# Ananas-core-0_9_2-no340G.net
KiCad netlist of a schematic drawn in EAGLE
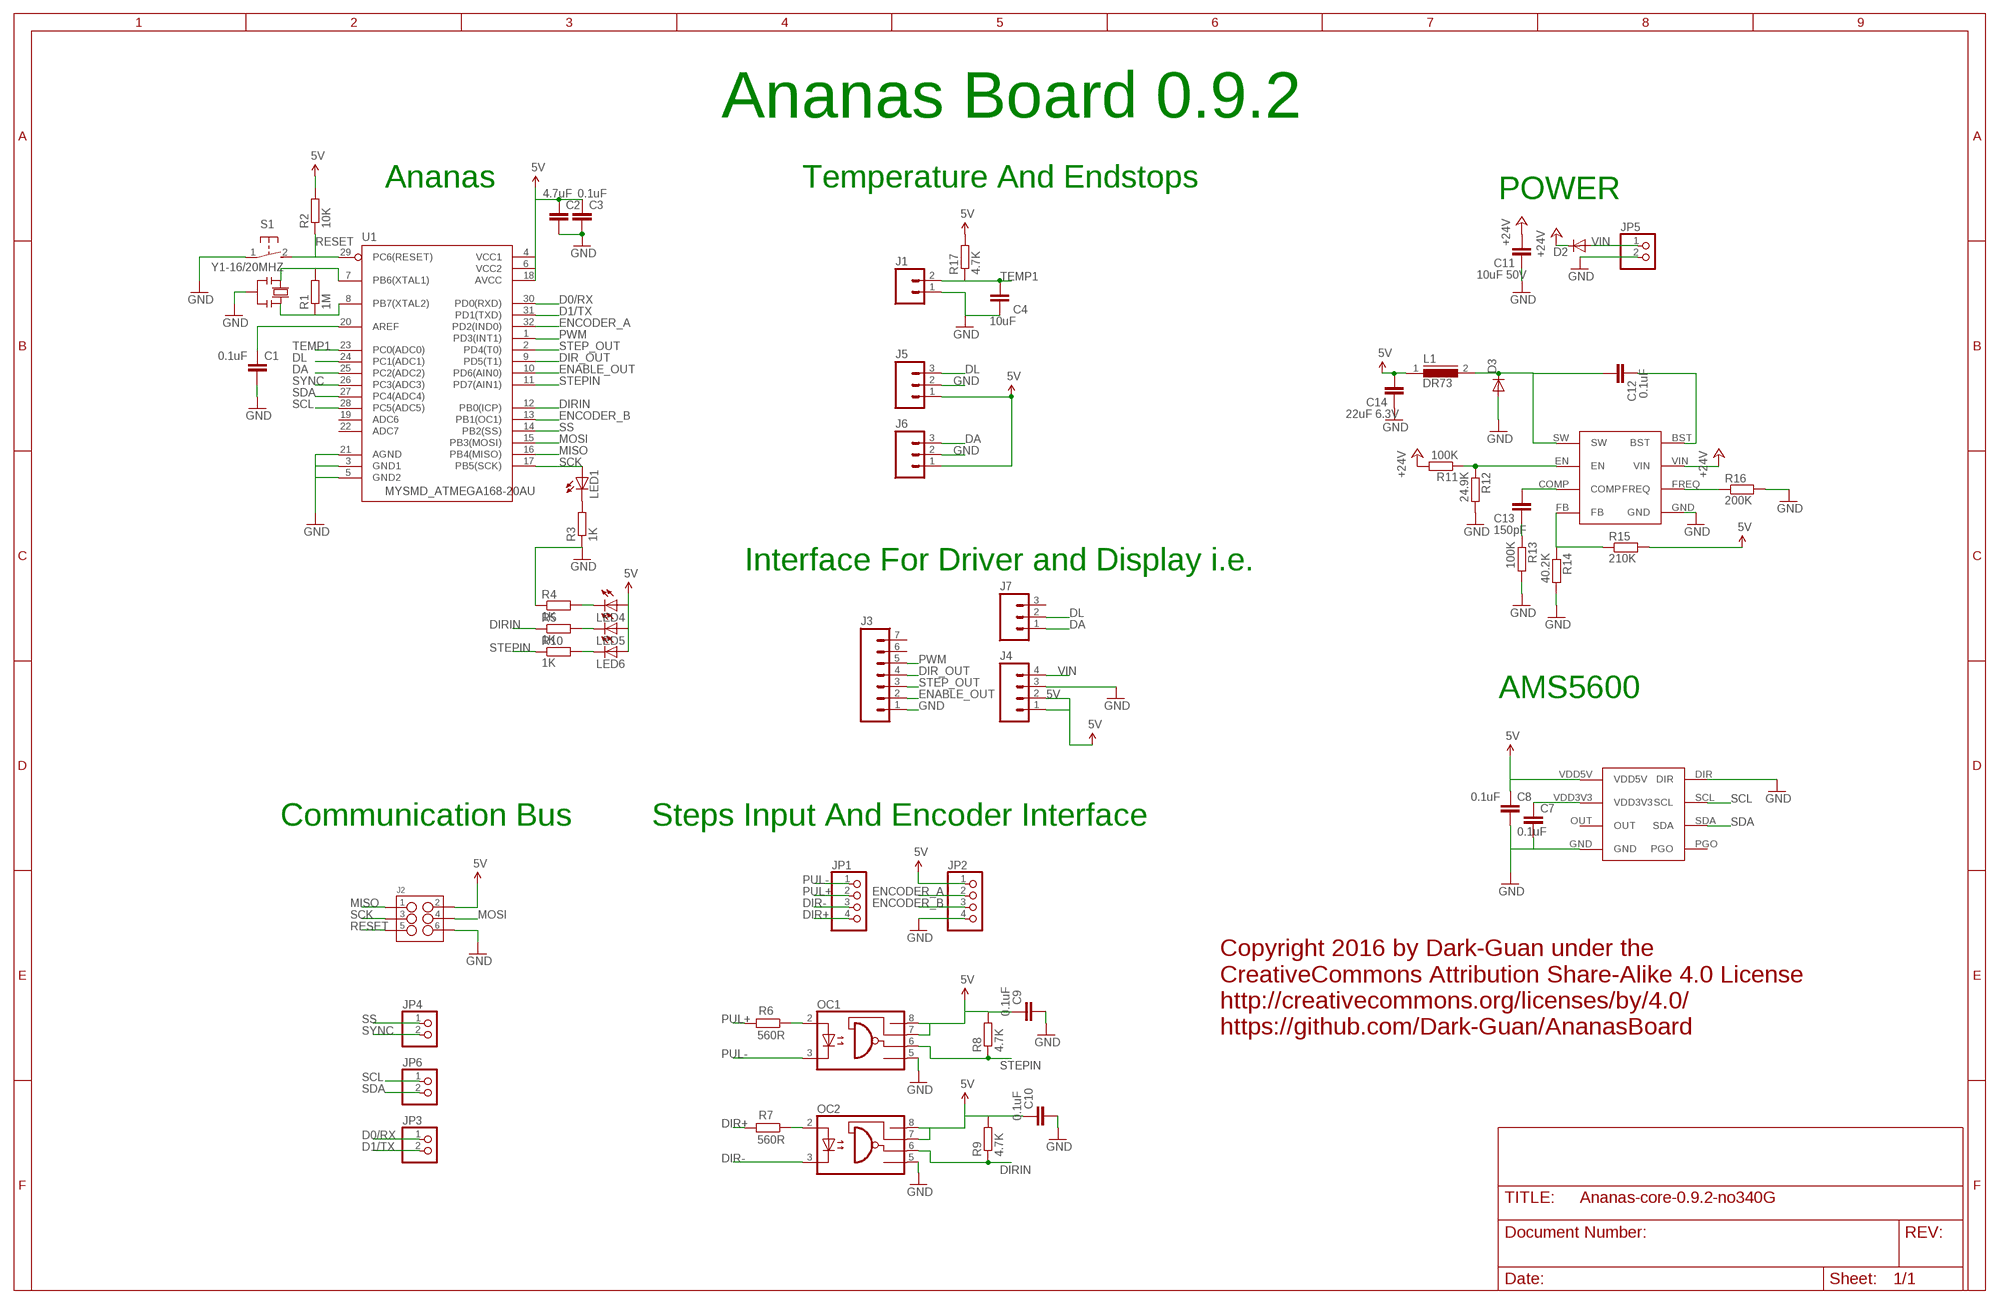
[diagram p0: schematic, sheet 1]

(export (version "E")
  (design (tool "Eeschema 10.0.6"))
  (components
    (comp (ref "C1")
      (value "0.1uF")
      (footprint "eagle-import:C0603K")
      (libsource (lib "eagle-import") (part "C-EUC0603K"))
    )
    (comp (ref "C2")
      (value "4.7uF")
      (footprint "eagle-import:C0603K")
      (libsource (lib "eagle-import") (part "C-EUC0603K"))
    )
    (comp (ref "C3")
      (value "0.1uF")
      (footprint "eagle-import:C0603K")
      (libsource (lib "eagle-import") (part "C-EUC0603K"))
    )
    (comp (ref "C4")
      (value "10uF")
      (footprint "eagle-import:C0603K")
      (libsource (lib "eagle-import") (part "C-EUC0603K"))
    )
    (comp (ref "C7")
      (value "0.1uF")
      (footprint "eagle-import:C0603K")
      (libsource (lib "eagle-import") (part "C-EUC0603K"))
    )
    (comp (ref "C8")
      (value "0.1uF")
      (footprint "eagle-import:C0603K")
      (libsource (lib "eagle-import") (part "C-EUC0603K"))
    )
    (comp (ref "C9")
      (value "0.1uF")
      (footprint "eagle-import:C0603K")
      (libsource (lib "eagle-import") (part "C-EUC0603K"))
    )
    (comp (ref "C10")
      (value "0.1uF")
      (footprint "eagle-import:C0603K")
      (libsource (lib "eagle-import") (part "C-EUC0603K"))
    )
    (comp (ref "C11")
      (value "10uF 50V")
      (footprint "eagle-import:C0805")
      (libsource (lib "eagle-import") (part "C-EUC0805"))
    )
    (comp (ref "C12")
      (value "0.1uF")
      (footprint "eagle-import:C0603K")
      (libsource (lib "eagle-import") (part "C-EUC0603K"))
    )
    (comp (ref "C13")
      (value "150pF")
      (footprint "eagle-import:C0603K")
      (libsource (lib "eagle-import") (part "C-EUC0603K"))
    )
    (comp (ref "C14")
      (value "22uF 6.3V")
      (footprint "eagle-import:C0805")
      (libsource (lib "eagle-import") (part "C-EUC0805"))
    )
    (comp (ref "D2")
      (value "DIODE_DIODE-SMB")
      (footprint "eagle-import:DIODE_SMB")
      (libsource (lib "eagle-import") (part "DIODE_DIODE-SMB"))
    )
    (comp (ref "D3")
      (value "DIODE_DIODE-SMB")
      (footprint "eagle-import:DIODE_SMB")
      (libsource (lib "eagle-import") (part "DIODE_DIODE-SMB"))
    )
    (comp (ref "J1")
      (value "M02PTH")
      (footprint "eagle-import:1X02")
      (libsource (lib "eagle-import") (part "M02PTH"))
    )
    (comp (ref "J2")
      (value "M03X2NO_SILK")
      (footprint "eagle-import:2X3-NS")
      (libsource (lib "eagle-import") (part "M03X2NO_SILK"))
    )
    (comp (ref "J3")
      (value "M07")
      (footprint "eagle-import:1X07")
      (libsource (lib "eagle-import") (part "M07"))
    )
    (comp (ref "J4")
      (value "M04PTH")
      (footprint "eagle-import:1X04")
      (libsource (lib "eagle-import") (part "M04PTH"))
    )
    (comp (ref "J5")
      (value "M03PTH")
      (footprint "eagle-import:1X03")
      (libsource (lib "eagle-import") (part "M03PTH"))
    )
    (comp (ref "J6")
      (value "M03PTH")
      (footprint "eagle-import:1X03")
      (libsource (lib "eagle-import") (part "M03PTH"))
    )
    (comp (ref "J7")
      (value "M03PTH")
      (footprint "eagle-import:1X03")
      (libsource (lib "eagle-import") (part "M03PTH"))
    )
    (comp (ref "JP1")
      (value "PINHD-1X4/OCT")
      (footprint "eagle-import:1X04_OCT")
      (libsource (lib "eagle-import") (part "PINHD-1X4/OCT"))
    )
    (comp (ref "JP2")
      (value "PINHD-1X4/OCT")
      (footprint "eagle-import:1X04_OCT")
      (libsource (lib "eagle-import") (part "PINHD-1X4/OCT"))
    )
    (comp (ref "JP3")
      (value "PINHD-1X2/OCT")
      (footprint "eagle-import:1X02_OCT")
      (libsource (lib "eagle-import") (part "PINHD-1X2/OCT"))
    )
    (comp (ref "JP4")
      (value "PINHD-1X2/OCT")
      (footprint "eagle-import:1X02_OCT")
      (libsource (lib "eagle-import") (part "PINHD-1X2/OCT"))
    )
    (comp (ref "JP5")
      (value "PINHD-1X2/OCT")
      (footprint "eagle-import:1X02_OCT")
      (libsource (lib "eagle-import") (part "PINHD-1X2/OCT"))
    )
    (comp (ref "JP6")
      (value "PINHD-1X2/OCT")
      (footprint "eagle-import:1X02_OCT")
      (libsource (lib "eagle-import") (part "PINHD-1X2/OCT"))
    )
    (comp (ref "L1")
      (value "DR73")
      (footprint "eagle-import:DR73")
      (libsource (lib "eagle-import") (part "DR73"))
    )
    (comp (ref "LED1")
      (value "LEDCHIPLED_0603")
      (footprint "eagle-import:CHIPLED_0603")
      (libsource (lib "eagle-import") (part "LEDCHIPLED_0603"))
    )
    (comp (ref "LED4")
      (value "LEDCHIPLED_0603")
      (footprint "eagle-import:CHIPLED_0603")
      (libsource (lib "eagle-import") (part "LEDCHIPLED_0603"))
    )
    (comp (ref "LED5")
      (value "LEDCHIPLED_0603")
      (footprint "eagle-import:CHIPLED_0603")
      (libsource (lib "eagle-import") (part "LEDCHIPLED_0603"))
    )
    (comp (ref "LED6")
      (value "LEDCHIPLED_0603")
      (footprint "eagle-import:CHIPLED_0603")
      (libsource (lib "eagle-import") (part "LEDCHIPLED_0603"))
    )
    (comp (ref "MP1854")
      (value "MP1584")
      (footprint "eagle-import:MP1584")
      (libsource (lib "eagle-import") (part "MP1584"))
    )
    (comp (ref "OC1")
      (value "OPTOCOUPLER_(2)_HCPL0600")
      (footprint "eagle-import:OPTOCOUPLER_(2)_SOIC08")
      (libsource (lib "eagle-import") (part "OPTOCOUPLER_(2)_HCPL0600"))
    )
    (comp (ref "OC2")
      (value "OPTOCOUPLER_(2)_HCPL0600")
      (footprint "eagle-import:OPTOCOUPLER_(2)_SOIC08")
      (libsource (lib "eagle-import") (part "OPTOCOUPLER_(2)_HCPL0600"))
    )
    (comp (ref "R1")
      (value "1M")
      (footprint "eagle-import:R0603")
      (libsource (lib "eagle-import") (part "R-EU_R0603"))
    )
    (comp (ref "R2")
      (value "10K")
      (footprint "eagle-import:R0603")
      (libsource (lib "eagle-import") (part "R-EU_R0603"))
    )
    (comp (ref "R3")
      (value "1K")
      (footprint "eagle-import:R0603")
      (libsource (lib "eagle-import") (part "R-EU_R0603"))
    )
    (comp (ref "R4")
      (value "1K")
      (footprint "eagle-import:R0603")
      (libsource (lib "eagle-import") (part "R-EU_R0603"))
    )
    (comp (ref "R5")
      (value "1K")
      (footprint "eagle-import:R0603")
      (libsource (lib "eagle-import") (part "R-EU_R0603"))
    )
    (comp (ref "R6")
      (value "560R")
      (footprint "eagle-import:R0603")
      (libsource (lib "eagle-import") (part "R-EU_R0603"))
    )
    (comp (ref "R7")
      (value "560R")
      (footprint "eagle-import:R0603")
      (libsource (lib "eagle-import") (part "R-EU_R0603"))
    )
    (comp (ref "R8")
      (value "4.7K")
      (footprint "eagle-import:R0603")
      (libsource (lib "eagle-import") (part "R-EU_R0603"))
    )
    (comp (ref "R9")
      (value "4.7K")
      (footprint "eagle-import:R0603")
      (libsource (lib "eagle-import") (part "R-EU_R0603"))
    )
    (comp (ref "R10")
      (value "1K")
      (footprint "eagle-import:R0603")
      (libsource (lib "eagle-import") (part "R-EU_R0603"))
    )
    (comp (ref "R11")
      (value "100K")
      (footprint "eagle-import:R0603")
      (libsource (lib "eagle-import") (part "R-EU_R0603"))
    )
    (comp (ref "R12")
      (value "24.9K")
      (footprint "eagle-import:R0603")
      (libsource (lib "eagle-import") (part "R-EU_R0603"))
    )
    (comp (ref "R13")
      (value "100K")
      (footprint "eagle-import:R0603")
      (libsource (lib "eagle-import") (part "R-EU_R0603"))
    )
    (comp (ref "R14")
      (value "40.2K")
      (footprint "eagle-import:R0603")
      (libsource (lib "eagle-import") (part "R-EU_R0603"))
    )
    (comp (ref "R15")
      (value "210K")
      (footprint "eagle-import:R0603")
      (libsource (lib "eagle-import") (part "R-EU_R0603"))
    )
    (comp (ref "R16")
      (value "200K")
      (footprint "eagle-import:R0603")
      (libsource (lib "eagle-import") (part "R-EU_R0603"))
    )
    (comp (ref "R17")
      (value "4.7K")
      (footprint "eagle-import:R0603")
      (libsource (lib "eagle-import") (part "R-EU_R0603"))
    )
    (comp (ref "S1")
      (value "31-XX")
      (footprint "eagle-import:B3F-31XX")
      (fields (field (name "MPN") "B3F-3100"))
      (libsource (lib "eagle-import") (part "31-XX"))
    )
    (comp (ref "U$1")
      (value "ARDUINO_AS5600")
      (footprint "eagle-import:ARDUINO_AS5600")
      (libsource (lib "eagle-import") (part "ARDUINO_AS5600"))
    )
    (comp (ref "U1")
      (value "MYSMD_ATMEGA168-20AU")
      (footprint "eagle-import:MYSMD_QFP032")
      (libsource (lib "eagle-import") (part "MYSMD_ATMEGA168-20AU"))
    )
    (comp (ref "Y1-16/20MHZ")
      (value "MYSMD2_RESONATORMU")
      (footprint "eagle-import:MYSMD2_RESONATOR")
      (libsource (lib "eagle-import") (part "MYSMD2_RESONATORMU"))
    )
  )
  (nets
    (net (code "1") (name "+24V") (class "Default")
      (node (ref "C11") (pin "2") (pinfunction "2_2") (pintype "passive"))
      (node (ref "D2") (pin "C") (pinfunction "C_C") (pintype "passive"))
      (node (ref "MP1854") (pin "VIN") (pinfunction "VIN_VIN") (pintype "bidirectional"))
      (node (ref "R11") (pin "2") (pinfunction "2_2") (pintype "passive"))
    )
    (net (code "2") (name "/D0{slash}RX") (class "Default")
      (node (ref "JP3") (pin "1") (pinfunction "1_1") (pintype "passive"))
      (node (ref "U1") (pin "30") (pinfunction "PD0(RXD)_30") (pintype "bidirectional"))
    )
    (net (code "3") (name "/D1{slash}TX") (class "Default")
      (node (ref "JP3") (pin "2") (pinfunction "2_2") (pintype "passive"))
      (node (ref "U1") (pin "31") (pinfunction "PD1(TXD)_31") (pintype "bidirectional"))
    )
    (net (code "4") (name "/DA") (class "Default")
      (node (ref "J6") (pin "3") (pinfunction "3_3") (pintype "passive"))
      (node (ref "J7") (pin "1") (pinfunction "1_1") (pintype "passive"))
      (node (ref "U1") (pin "25") (pinfunction "PC2(ADC2)_25") (pintype "passive"))
    )
    (net (code "5") (name "/DIR+") (class "Default")
      (node (ref "JP1") (pin "4") (pinfunction "4_4") (pintype "passive"))
      (node (ref "R7") (pin "2") (pinfunction "2_2") (pintype "passive"))
    )
    (net (code "6") (name "/DIR-") (class "Default")
      (node (ref "JP1") (pin "3") (pinfunction "3_3") (pintype "passive"))
      (node (ref "OC2") (pin "3") (pinfunction "C_3") (pintype "passive"))
    )
    (net (code "7") (name "/DIRIN") (class "Default")
      (node (ref "OC2") (pin "6") (pinfunction "VO_6") (pintype "passive"))
      (node (ref "R5") (pin "1") (pinfunction "1_1") (pintype "passive"))
      (node (ref "R9") (pin "1") (pinfunction "1_1") (pintype "passive"))
      (node (ref "U1") (pin "12") (pinfunction "PB0(ICP)_12") (pintype "bidirectional"))
    )
    (net (code "8") (name "/DIR_OUT") (class "Default")
      (node (ref "J3") (pin "4") (pinfunction "4_4") (pintype "passive"))
      (node (ref "U1") (pin "9") (pinfunction "PD5(T1)_9") (pintype "bidirectional"))
    )
    (net (code "9") (name "/DL") (class "Default")
      (node (ref "J5") (pin "3") (pinfunction "3_3") (pintype "passive"))
      (node (ref "J7") (pin "2") (pinfunction "2_2") (pintype "passive"))
      (node (ref "U1") (pin "24") (pinfunction "PC1(ADC1)_24") (pintype "passive"))
    )
    (net (code "10") (name "/ENABLE_OUT") (class "Default")
      (node (ref "J3") (pin "2") (pinfunction "2_2") (pintype "passive"))
      (node (ref "U1") (pin "10") (pinfunction "PD6(AIN0)_10") (pintype "bidirectional"))
    )
    (net (code "11") (name "/ENCODER_A") (class "Default")
      (node (ref "JP2") (pin "2") (pinfunction "2_2") (pintype "passive"))
      (node (ref "U1") (pin "32") (pinfunction "PD2(IND0)_32") (pintype "bidirectional"))
    )
    (net (code "12") (name "/ENCODER_B") (class "Default")
      (node (ref "JP2") (pin "3") (pinfunction "3_3") (pintype "passive"))
      (node (ref "U1") (pin "13") (pinfunction "PB1(OC1)_13") (pintype "bidirectional"))
    )
    (net (code "13") (name "/MISO") (class "Default")
      (node (ref "J2") (pin "1") (pinfunction "1_1") (pintype "bidirectional"))
      (node (ref "U1") (pin "16") (pinfunction "PB4(MISO)_16") (pintype "bidirectional"))
    )
    (net (code "14") (name "/MOSI") (class "Default")
      (node (ref "J2") (pin "4") (pinfunction "4_4") (pintype "bidirectional"))
      (node (ref "U1") (pin "15") (pinfunction "PB3(MOSI)_15") (pintype "bidirectional"))
    )
    (net (code "15") (name "/PUL+") (class "Default")
      (node (ref "JP1") (pin "2") (pinfunction "2_2") (pintype "passive"))
      (node (ref "R6") (pin "2") (pinfunction "2_2") (pintype "passive"))
    )
    (net (code "16") (name "/PUL-") (class "Default")
      (node (ref "JP1") (pin "1") (pinfunction "1_1") (pintype "passive"))
      (node (ref "OC1") (pin "3") (pinfunction "C_3") (pintype "passive"))
    )
    (net (code "17") (name "/PWM") (class "Default")
      (node (ref "J3") (pin "5") (pinfunction "5_5") (pintype "passive"))
      (node (ref "U1") (pin "1") (pinfunction "PD3(INT1)_1") (pintype "bidirectional"))
    )
    (net (code "18") (name "/RESET") (class "Default")
      (node (ref "J2") (pin "5") (pinfunction "5_5") (pintype "bidirectional"))
      (node (ref "R2") (pin "1") (pinfunction "1_1") (pintype "passive"))
      (node (ref "S1") (pin "2") (pinfunction "S_2") (pintype "passive"))
      (node (ref "U1") (pin "29") (pinfunction "PC6(RESET)_29") (pintype "bidirectional"))
    )
    (net (code "19") (name "/SCK") (class "Default")
      (node (ref "J2") (pin "3") (pinfunction "3_3") (pintype "bidirectional"))
      (node (ref "LED1") (pin "A") (pinfunction "A_A") (pintype "passive"))
      (node (ref "U1") (pin "17") (pinfunction "PB5(SCK)_17") (pintype "bidirectional"))
    )
    (net (code "20") (name "/SCL") (class "Default")
      (node (ref "JP6") (pin "1") (pinfunction "1_1") (pintype "passive"))
      (node (ref "U$1") (pin "SCL") (pinfunction "SCL_SCL") (pintype "bidirectional"))
      (node (ref "U1") (pin "28") (pinfunction "PC5(ADC5)_28") (pintype "passive"))
    )
    (net (code "21") (name "/SDA") (class "Default")
      (node (ref "JP6") (pin "2") (pinfunction "2_2") (pintype "passive"))
      (node (ref "U$1") (pin "SDA") (pinfunction "SDA_SDA") (pintype "bidirectional"))
      (node (ref "U1") (pin "27") (pinfunction "PC4(ADC4)_27") (pintype "passive"))
    )
    (net (code "22") (name "/SS") (class "Default")
      (node (ref "JP4") (pin "1") (pinfunction "1_1") (pintype "passive"))
      (node (ref "U1") (pin "14") (pinfunction "PB2(SS)_14") (pintype "bidirectional"))
    )
    (net (code "23") (name "/STEPIN") (class "Default")
      (node (ref "OC1") (pin "6") (pinfunction "VO_6") (pintype "passive"))
      (node (ref "R10") (pin "1") (pinfunction "1_1") (pintype "passive"))
      (node (ref "R8") (pin "1") (pinfunction "1_1") (pintype "passive"))
      (node (ref "U1") (pin "11") (pinfunction "PD7(AIN1)_11") (pintype "bidirectional"))
    )
    (net (code "24") (name "/STEP_OUT") (class "Default")
      (node (ref "J3") (pin "3") (pinfunction "3_3") (pintype "passive"))
      (node (ref "U1") (pin "2") (pinfunction "PD4(T0)_2") (pintype "bidirectional"))
    )
    (net (code "25") (name "/SYNC") (class "Default")
      (node (ref "JP4") (pin "2") (pinfunction "2_2") (pintype "passive"))
      (node (ref "U1") (pin "26") (pinfunction "PC3(ADC3)_26") (pintype "passive"))
    )
    (net (code "26") (name "/TEMP1") (class "Default")
      (node (ref "C4") (pin "2") (pinfunction "2_2") (pintype "passive"))
      (node (ref "J1") (pin "2") (pinfunction "2_2") (pintype "passive"))
      (node (ref "R17") (pin "1") (pinfunction "1_1") (pintype "passive"))
      (node (ref "U1") (pin "23") (pinfunction "PC0(ADC0)_23") (pintype "passive"))
    )
    (net (code "27") (name "/VIN") (class "Default")
      (node (ref "D2") (pin "A") (pinfunction "A_A") (pintype "passive"))
      (node (ref "J4") (pin "4") (pinfunction "4_4") (pintype "passive"))
      (node (ref "JP5") (pin "1") (pinfunction "1_1") (pintype "passive"))
    )
    (net (code "28") (name "5V") (class "Default")
      (node (ref "C10") (pin "1") (pinfunction "1_1") (pintype "passive"))
      (node (ref "C14") (pin "2") (pinfunction "2_2") (pintype "passive"))
      (node (ref "C2") (pin "1") (pinfunction "1_1") (pintype "passive"))
      (node (ref "C3") (pin "1") (pinfunction "1_1") (pintype "passive"))
      (node (ref "C8") (pin "1") (pinfunction "1_1") (pintype "passive"))
      (node (ref "C9") (pin "1") (pinfunction "1_1") (pintype "passive"))
      (node (ref "J2") (pin "2") (pinfunction "2_2") (pintype "bidirectional"))
      (node (ref "J4") (pin "1") (pinfunction "1_1") (pintype "passive"))
      (node (ref "J4") (pin "2") (pinfunction "2_2") (pintype "passive"))
      (node (ref "J5") (pin "1") (pinfunction "1_1") (pintype "passive"))
      (node (ref "J6") (pin "1") (pinfunction "1_1") (pintype "passive"))
      (node (ref "JP2") (pin "1") (pinfunction "1_1") (pintype "passive"))
      (node (ref "L1") (pin "1") (pinfunction "1_1") (pintype "passive"))
      (node (ref "LED4") (pin "A") (pinfunction "A_A") (pintype "passive"))
      (node (ref "LED5") (pin "A") (pinfunction "A_A") (pintype "passive"))
      (node (ref "LED6") (pin "A") (pinfunction "A_A") (pintype "passive"))
      (node (ref "OC1") (pin "7") (pinfunction "VE_7") (pintype "passive"))
      (node (ref "OC1") (pin "8") (pinfunction "VCC_8") (pintype "passive"))
      (node (ref "OC2") (pin "7") (pinfunction "VE_7") (pintype "passive"))
      (node (ref "OC2") (pin "8") (pinfunction "VCC_8") (pintype "passive"))
      (node (ref "R15") (pin "2") (pinfunction "2_2") (pintype "passive"))
      (node (ref "R17") (pin "2") (pinfunction "2_2") (pintype "passive"))
      (node (ref "R2") (pin "2") (pinfunction "2_2") (pintype "passive"))
      (node (ref "R8") (pin "2") (pinfunction "2_2") (pintype "passive"))
      (node (ref "R9") (pin "2") (pinfunction "2_2") (pintype "passive"))
      (node (ref "U$1") (pin "VDD5V") (pinfunction "VDD5V_VDD5V") (pintype "bidirectional"))
      (node (ref "U1") (pin "18") (pinfunction "AVCC_18") (pintype "passive"))
      (node (ref "U1") (pin "4") (pinfunction "VCC1_4") (pintype "power_in"))
      (node (ref "U1") (pin "6") (pinfunction "VCC2_6") (pintype "power_in"))
    )
    (net (code "29") (name "GND") (class "Default")
      (node (ref "C1") (pin "2") (pinfunction "2_2") (pintype "passive"))
      (node (ref "C10") (pin "2") (pinfunction "2_2") (pintype "passive"))
      (node (ref "C11") (pin "1") (pinfunction "1_1") (pintype "passive"))
      (node (ref "C14") (pin "1") (pinfunction "1_1") (pintype "passive"))
      (node (ref "C2") (pin "2") (pinfunction "2_2") (pintype "passive"))
      (node (ref "C3") (pin "2") (pinfunction "2_2") (pintype "passive"))
      (node (ref "C4") (pin "1") (pinfunction "1_1") (pintype "passive"))
      (node (ref "C7") (pin "2") (pinfunction "2_2") (pintype "passive"))
      (node (ref "C8") (pin "2") (pinfunction "2_2") (pintype "passive"))
      (node (ref "C9") (pin "2") (pinfunction "2_2") (pintype "passive"))
      (node (ref "D3") (pin "A") (pinfunction "A_A") (pintype "passive"))
      (node (ref "J1") (pin "1") (pinfunction "1_1") (pintype "passive"))
      (node (ref "J2") (pin "6") (pinfunction "6_6") (pintype "bidirectional"))
      (node (ref "J3") (pin "1") (pinfunction "1_1") (pintype "passive"))
      (node (ref "J4") (pin "3") (pinfunction "3_3") (pintype "passive"))
      (node (ref "J5") (pin "2") (pinfunction "2_2") (pintype "passive"))
      (node (ref "J6") (pin "2") (pinfunction "2_2") (pintype "passive"))
      (node (ref "JP2") (pin "4") (pinfunction "4_4") (pintype "passive"))
      (node (ref "JP5") (pin "2") (pinfunction "2_2") (pintype "passive"))
      (node (ref "MP1854") (pin "GND") (pinfunction "GND_GND") (pintype "bidirectional"))
      (node (ref "OC1") (pin "5") (pinfunction "GND_5") (pintype "passive"))
      (node (ref "OC2") (pin "5") (pinfunction "GND_5") (pintype "passive"))
      (node (ref "R12") (pin "2") (pinfunction "2_2") (pintype "passive"))
      (node (ref "R13") (pin "2") (pinfunction "2_2") (pintype "passive"))
      (node (ref "R14") (pin "2") (pinfunction "2_2") (pintype "passive"))
      (node (ref "R16") (pin "2") (pinfunction "2_2") (pintype "passive"))
      (node (ref "R3") (pin "1") (pinfunction "1_1") (pintype "passive"))
      (node (ref "R4") (pin "1") (pinfunction "1_1") (pintype "passive"))
      (node (ref "S1") (pin "1") (pinfunction "P_1") (pintype "passive"))
      (node (ref "U$1") (pin "DIR") (pinfunction "DIR_DIR") (pintype "bidirectional"))
      (node (ref "U$1") (pin "GND") (pinfunction "GND_GND") (pintype "bidirectional"))
      (node (ref "U1") (pin "21") (pinfunction "AGND_21") (pintype "passive"))
      (node (ref "U1") (pin "3") (pinfunction "GND1_3") (pintype "power_in"))
      (node (ref "U1") (pin "5") (pinfunction "GND2_5") (pintype "power_in"))
      (node (ref "Y1-16/20MHZ") (pin "2") (pinfunction "2_2") (pintype "passive"))
    )
    (net (code "30") (name "Net-(C7-Pad1)") (class "Default")
      (node (ref "C7") (pin "1") (pinfunction "1_1") (pintype "passive"))
      (node (ref "U$1") (pin "VDD3V3") (pinfunction "VDD3V3_VDD3V3") (pintype "bidirectional"))
    )
    (net (code "31") (name "Net-(C12-Pad1)") (class "Default")
      (node (ref "C12") (pin "1") (pinfunction "1_1") (pintype "passive"))
      (node (ref "MP1854") (pin "BST") (pinfunction "BST_BST") (pintype "bidirectional"))
    )
    (net (code "32") (name "Net-(C12-Pad2)") (class "Default")
      (node (ref "C12") (pin "2") (pinfunction "2_2") (pintype "passive"))
      (node (ref "D3") (pin "C") (pinfunction "C_C") (pintype "passive"))
      (node (ref "L1") (pin "2") (pinfunction "2_2") (pintype "passive"))
      (node (ref "MP1854") (pin "SW") (pinfunction "SW_SW") (pintype "bidirectional"))
    )
    (net (code "33") (name "Net-(C13-Pad1)") (class "Default")
      (node (ref "C13") (pin "1") (pinfunction "1_1") (pintype "passive"))
      (node (ref "R13") (pin "1") (pinfunction "1_1") (pintype "passive"))
    )
    (net (code "34") (name "Net-(C13-Pad2)") (class "Default")
      (node (ref "C13") (pin "2") (pinfunction "2_2") (pintype "passive"))
      (node (ref "MP1854") (pin "COMP") (pinfunction "COMP_COMP") (pintype "bidirectional"))
    )
    (net (code "35") (name "Net-(LED1-PadC)") (class "Default")
      (node (ref "LED1") (pin "C") (pinfunction "C_C") (pintype "passive"))
      (node (ref "R3") (pin "2") (pinfunction "2_2") (pintype "passive"))
    )
    (net (code "36") (name "Net-(LED4-PadC)") (class "Default")
      (node (ref "LED4") (pin "C") (pinfunction "C_C") (pintype "passive"))
      (node (ref "R4") (pin "2") (pinfunction "2_2") (pintype "passive"))
    )
    (net (code "37") (name "Net-(LED5-PadC)") (class "Default")
      (node (ref "LED5") (pin "C") (pinfunction "C_C") (pintype "passive"))
      (node (ref "R5") (pin "2") (pinfunction "2_2") (pintype "passive"))
    )
    (net (code "38") (name "Net-(LED6-PadC)") (class "Default")
      (node (ref "LED6") (pin "C") (pinfunction "C_C") (pintype "passive"))
      (node (ref "R10") (pin "2") (pinfunction "2_2") (pintype "passive"))
    )
    (net (code "39") (name "Net-(MP1854-PadEN)") (class "Default")
      (node (ref "MP1854") (pin "EN") (pinfunction "EN_EN") (pintype "bidirectional"))
      (node (ref "R11") (pin "1") (pinfunction "1_1") (pintype "passive"))
      (node (ref "R12") (pin "1") (pinfunction "1_1") (pintype "passive"))
    )
    (net (code "40") (name "Net-(MP1854-PadFB)") (class "Default")
      (node (ref "MP1854") (pin "FB") (pinfunction "FB_FB") (pintype "bidirectional"))
      (node (ref "R14") (pin "1") (pinfunction "1_1") (pintype "passive"))
      (node (ref "R15") (pin "1") (pinfunction "1_1") (pintype "passive"))
    )
    (net (code "41") (name "Net-(MP1854-PadFREQ)") (class "Default")
      (node (ref "MP1854") (pin "FREQ") (pinfunction "FREQ_FREQ") (pintype "bidirectional"))
      (node (ref "R16") (pin "1") (pinfunction "1_1") (pintype "passive"))
    )
    (net (code "42") (name "Net-(OC1-A)") (class "Default")
      (node (ref "OC1") (pin "2") (pinfunction "A_2") (pintype "passive"))
      (node (ref "R6") (pin "1") (pinfunction "1_1") (pintype "passive"))
    )
    (net (code "43") (name "Net-(OC2-A)") (class "Default")
      (node (ref "OC2") (pin "2") (pinfunction "A_2") (pintype "passive"))
      (node (ref "R7") (pin "1") (pinfunction "1_1") (pintype "passive"))
    )
    (net (code "44") (name "Net-(U1-AREF)") (class "Default")
      (node (ref "C1") (pin "1") (pinfunction "1_1") (pintype "passive"))
      (node (ref "U1") (pin "20") (pinfunction "AREF_20") (pintype "passive"))
    )
    (net (code "45") (name "Net-(U1-PB6(XTAL1))") (class "Default")
      (node (ref "R1") (pin "2") (pinfunction "2_2") (pintype "passive"))
      (node (ref "U1") (pin "7") (pinfunction "PB6(XTAL1)_7") (pintype "passive"))
      (node (ref "Y1-16/20MHZ") (pin "1") (pinfunction "1_1") (pintype "passive"))
    )
    (net (code "46") (name "Net-(U1-PB7(XTAL2))") (class "Default")
      (node (ref "R1") (pin "1") (pinfunction "1_1") (pintype "passive"))
      (node (ref "U1") (pin "8") (pinfunction "PB7(XTAL2)_8") (pintype "passive"))
      (node (ref "Y1-16/20MHZ") (pin "3") (pinfunction "3_3") (pintype "passive"))
    )
    (net (code "47") (name "unconnected-(J3-Pad6)") (class "Default")
      (node (ref "J3") (pin "6") (pinfunction "6_6") (pintype "passive"))
    )
    (net (code "48") (name "unconnected-(J3-Pad7)") (class "Default")
      (node (ref "J3") (pin "7") (pinfunction "7_7") (pintype "passive"))
    )
    (net (code "49") (name "unconnected-(J7-Pad3)") (class "Default")
      (node (ref "J7") (pin "3") (pinfunction "3_3") (pintype "passive"))
    )
    (net (code "50") (name "unconnected-(U$1-PadOUT)") (class "Default")
      (node (ref "U$1") (pin "OUT") (pinfunction "OUT_OUT") (pintype "bidirectional"))
    )
    (net (code "51") (name "unconnected-(U$1-PadPGO)") (class "Default")
      (node (ref "U$1") (pin "PGO") (pinfunction "PGO_PGO") (pintype "bidirectional"))
    )
    (net (code "52") (name "unconnected-(U1-ADC6-Pad19)") (class "Default")
      (node (ref "U1") (pin "19") (pinfunction "ADC6_19") (pintype "passive"))
    )
    (net (code "53") (name "unconnected-(U1-ADC7-Pad22)") (class "Default")
      (node (ref "U1") (pin "22") (pinfunction "ADC7_22") (pintype "passive"))
    )
  )
)
